# AMS00x.net
KiCad netlist of a schematic drawn in EAGLE
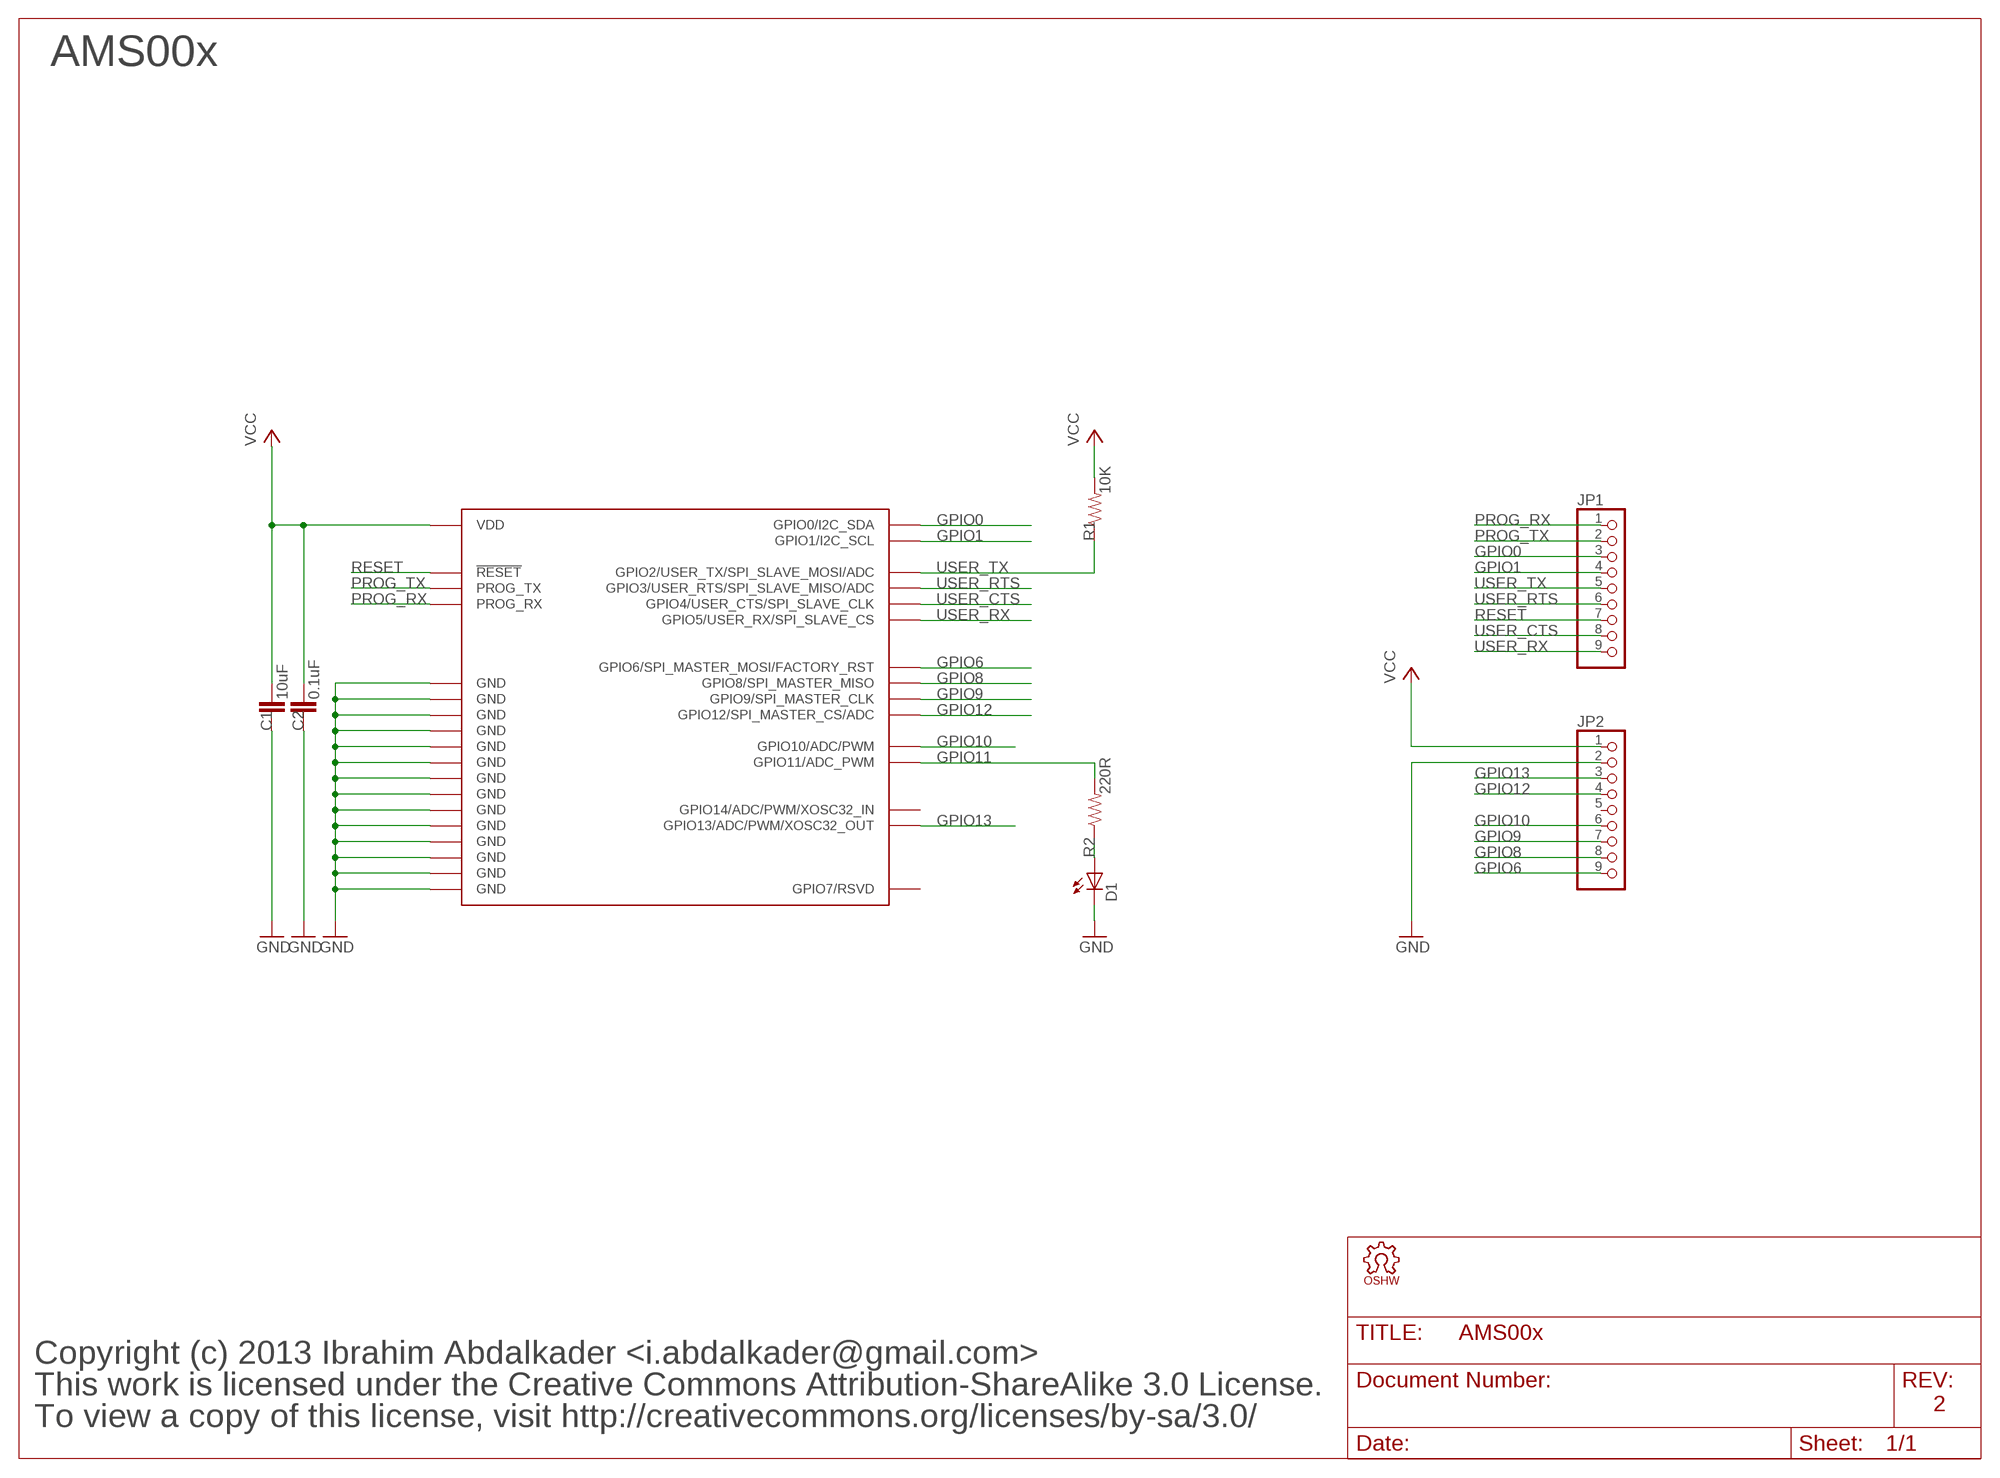
[diagram p0: schematic, sheet 1]

(export (version "E")
  (design (tool "Eeschema 10.0.6"))
  (components
    (comp (ref "C1")
      (value "10uF")
      (footprint "eagle-import:0603-CAP")
      (libsource (lib "eagle-import") (part "CAP0603-CAP"))
    )
    (comp (ref "C2")
      (value "0.1uF")
      (footprint "eagle-import:0603-CAP")
      (libsource (lib "eagle-import") (part "CAP0603-CAP"))
    )
    (comp (ref "D1")
      (value "LED0603")
      (footprint "eagle-import:LED-0603")
      (libsource (lib "eagle-import") (part "LED0603"))
    )
    (comp (ref "JP1")
      (value "PINHD-1X9")
      (footprint "eagle-import:1X09")
      (libsource (lib "eagle-import") (part "PINHD-1X9"))
    )
    (comp (ref "JP2")
      (value "PINHD-1X9")
      (footprint "eagle-import:1X09")
      (libsource (lib "eagle-import") (part "PINHD-1X9"))
    )
    (comp (ref "LOGO1")
      (value "OSHW_LOGO_6MILX0100-NT")
      (footprint "eagle-import:OSHW_6X100_NOTEXT")
      (libsource (lib "eagle-import") (part "OSHW_LOGO_6MILX0100-NT"))
    )
    (comp (ref "R1")
      (value "10K")
      (footprint "eagle-import:0603-RES")
      (libsource (lib "eagle-import") (part "RESISTOR0603-RES"))
    )
    (comp (ref "R2")
      (value "220R")
      (footprint "eagle-import:0603-RES")
      (libsource (lib "eagle-import") (part "RESISTOR0603-RES"))
    )
    (comp (ref "U$3")
      (value "AMS00X")
      (footprint "eagle-import:AMS00X")
      (libsource (lib "eagle-import") (part "AMS00X"))
    )
  )
  (nets
    (net (code "1") (name "/GPIO0") (class "Default")
      (node (ref "JP1") (pin "3") (pinfunction "3_3") (pintype "passive"))
      (node (ref "U$3") (pin "P$4") (pinfunction "GPIO0/I2C_SDA_P$4") (pintype "bidirectional"))
    )
    (net (code "2") (name "/GPIO1") (class "Default")
      (node (ref "JP1") (pin "4") (pinfunction "4_4") (pintype "passive"))
      (node (ref "U$3") (pin "P$5") (pinfunction "GPIO1/I2C_SCL_P$5") (pintype "bidirectional"))
    )
    (net (code "3") (name "/GPIO6") (class "Default")
      (node (ref "JP2") (pin "9") (pinfunction "9_9") (pintype "passive"))
      (node (ref "U$3") (pin "P$11") (pinfunction "GPIO6/SPI_MASTER_MOSI/FACTORY_RST_P$11") (pintype "bidirectional"))
    )
    (net (code "4") (name "/GPIO8") (class "Default")
      (node (ref "JP2") (pin "8") (pinfunction "8_8") (pintype "passive"))
      (node (ref "U$3") (pin "P$13") (pinfunction "GPIO8/SPI_MASTER_MISO_P$13") (pintype "bidirectional"))
    )
    (net (code "5") (name "/GPIO9") (class "Default")
      (node (ref "JP2") (pin "7") (pinfunction "7_7") (pintype "passive"))
      (node (ref "U$3") (pin "P$14") (pinfunction "GPIO9/SPI_MASTER_CLK_P$14") (pintype "bidirectional"))
    )
    (net (code "6") (name "/GPIO10") (class "Default")
      (node (ref "JP2") (pin "6") (pinfunction "6_6") (pintype "passive"))
      (node (ref "U$3") (pin "P$15") (pinfunction "GPIO10/ADC/PWM_P$15") (pintype "bidirectional"))
    )
    (net (code "7") (name "/GPIO11") (class "Default")
      (node (ref "R2") (pin "2") (pinfunction "2_2") (pintype "passive"))
      (node (ref "U$3") (pin "P$16") (pinfunction "GPIO11/ADC_PWM_P$16") (pintype "bidirectional"))
    )
    (net (code "8") (name "/GPIO12") (class "Default")
      (node (ref "JP2") (pin "4") (pinfunction "4_4") (pintype "passive"))
      (node (ref "U$3") (pin "P$17") (pinfunction "GPIO12/SPI_MASTER_CS/ADC_P$17") (pintype "bidirectional"))
    )
    (net (code "9") (name "/GPIO13") (class "Default")
      (node (ref "JP2") (pin "3") (pinfunction "3_3") (pintype "passive"))
      (node (ref "U$3") (pin "P$18") (pinfunction "GPIO13/ADC/PWM/XOSC32_OUT_P$18") (pintype "bidirectional"))
    )
    (net (code "10") (name "/PROG_RX") (class "Default")
      (node (ref "JP1") (pin "1") (pinfunction "1_1") (pintype "passive"))
      (node (ref "U$3") (pin "P$2") (pinfunction "PROG_RX_P$2") (pintype "bidirectional"))
    )
    (net (code "11") (name "/PROG_TX") (class "Default")
      (node (ref "JP1") (pin "2") (pinfunction "2_2") (pintype "passive"))
      (node (ref "U$3") (pin "P$3") (pinfunction "PROG_TX_P$3") (pintype "bidirectional"))
    )
    (net (code "12") (name "/RESET") (class "Default")
      (node (ref "JP1") (pin "7") (pinfunction "7_7") (pintype "passive"))
      (node (ref "U$3") (pin "P$8") (pinfunction "~{RESET}_P$8") (pintype "bidirectional"))
    )
    (net (code "13") (name "/USER_CTS") (class "Default")
      (node (ref "JP1") (pin "8") (pinfunction "8_8") (pintype "passive"))
      (node (ref "U$3") (pin "P$9") (pinfunction "GPIO4/USER_CTS/SPI_SLAVE_CLK_P$9") (pintype "bidirectional"))
    )
    (net (code "14") (name "/USER_RTS") (class "Default")
      (node (ref "JP1") (pin "6") (pinfunction "6_6") (pintype "passive"))
      (node (ref "U$3") (pin "P$7") (pinfunction "GPIO3/USER_RTS/SPI_SLAVE_MISO/ADC_P$7") (pintype "bidirectional"))
    )
    (net (code "15") (name "/USER_RX") (class "Default")
      (node (ref "JP1") (pin "9") (pinfunction "9_9") (pintype "passive"))
      (node (ref "U$3") (pin "P$10") (pinfunction "GPIO5/USER_RX/SPI_SLAVE_CS_P$10") (pintype "bidirectional"))
    )
    (net (code "16") (name "/USER_TX") (class "Default")
      (node (ref "JP1") (pin "5") (pinfunction "5_5") (pintype "passive"))
      (node (ref "R1") (pin "1") (pinfunction "1_1") (pintype "passive"))
      (node (ref "U$3") (pin "P$6") (pinfunction "GPIO2/USER_TX/SPI_SLAVE_MOSI/ADC_P$6") (pintype "bidirectional"))
    )
    (net (code "17") (name "GND") (class "Default")
      (node (ref "C1") (pin "1") (pinfunction "1_1") (pintype "passive"))
      (node (ref "C2") (pin "1") (pinfunction "1_1") (pintype "passive"))
      (node (ref "D1") (pin "C") (pinfunction "C_C") (pintype "passive"))
      (node (ref "JP2") (pin "2") (pinfunction "2_2") (pintype "passive"))
      (node (ref "U$3") (pin "P$1") (pinfunction "GND_P$1") (pintype "power_in"))
      (node (ref "U$3") (pin "P$19") (pinfunction "GND_P$19") (pintype "power_in"))
      (node (ref "U$3") (pin "P$22") (pinfunction "GND_P$22") (pintype "power_in"))
      (node (ref "U$3") (pin "P$23") (pinfunction "GND_P$23") (pintype "power_in"))
      (node (ref "U$3") (pin "P$24") (pinfunction "GND_P$24") (pintype "power_in"))
      (node (ref "U$3") (pin "P$25") (pinfunction "GND_P$25") (pintype "power_in"))
      (node (ref "U$3") (pin "P$26") (pinfunction "GND_P$26") (pintype "power_in"))
      (node (ref "U$3") (pin "P$27") (pinfunction "GND_P$27") (pintype "power_in"))
      (node (ref "U$3") (pin "P$28") (pinfunction "GND_P$28") (pintype "power_in"))
      (node (ref "U$3") (pin "P$29") (pinfunction "GND_P$29") (pintype "power_in"))
      (node (ref "U$3") (pin "P$30") (pinfunction "GND_P$30") (pintype "power_in"))
      (node (ref "U$3") (pin "P$31") (pinfunction "GND_P$31") (pintype "power_in"))
      (node (ref "U$3") (pin "P$32") (pinfunction "GND_P$32") (pintype "power_in"))
      (node (ref "U$3") (pin "P$33") (pinfunction "GND_P$33") (pintype "power_in"))
    )
    (net (code "18") (name "Net-(D1-PadA)") (class "Default")
      (node (ref "D1") (pin "A") (pinfunction "A_A") (pintype "passive"))
      (node (ref "R2") (pin "1") (pinfunction "1_1") (pintype "passive"))
    )
    (net (code "19") (name "VCC") (class "Default")
      (node (ref "C1") (pin "2") (pinfunction "2_2") (pintype "passive"))
      (node (ref "C2") (pin "2") (pinfunction "2_2") (pintype "passive"))
      (node (ref "JP2") (pin "1") (pinfunction "1_1") (pintype "passive"))
      (node (ref "R1") (pin "2") (pinfunction "2_2") (pintype "passive"))
      (node (ref "U$3") (pin "P$21") (pinfunction "VDD_P$21") (pintype "power_in"))
    )
    (net (code "20") (name "unconnected-(JP2-Pad5)") (class "Default")
      (node (ref "JP2") (pin "5") (pinfunction "5_5") (pintype "passive"))
    )
    (net (code "21") (name "unconnected-(U$3-GPIO7{slash}RSVD-PadP$12)") (class "Default")
      (node (ref "U$3") (pin "P$12") (pinfunction "GPIO7/RSVD_P$12") (pintype "no_connect"))
    )
    (net (code "22") (name "unconnected-(U$3-GPIO14{slash}ADC{slash}PWM{slash}XOSC32_IN-PadP$20)") (class "Default")
      (node (ref "U$3") (pin "P$20") (pinfunction "GPIO14/ADC/PWM/XOSC32_IN_P$20") (pintype "bidirectional"))
    )
  )
)
